# dual-led-wireless-dimmer-rev-c.net
KiCad netlist of a schematic drawn in EAGLE
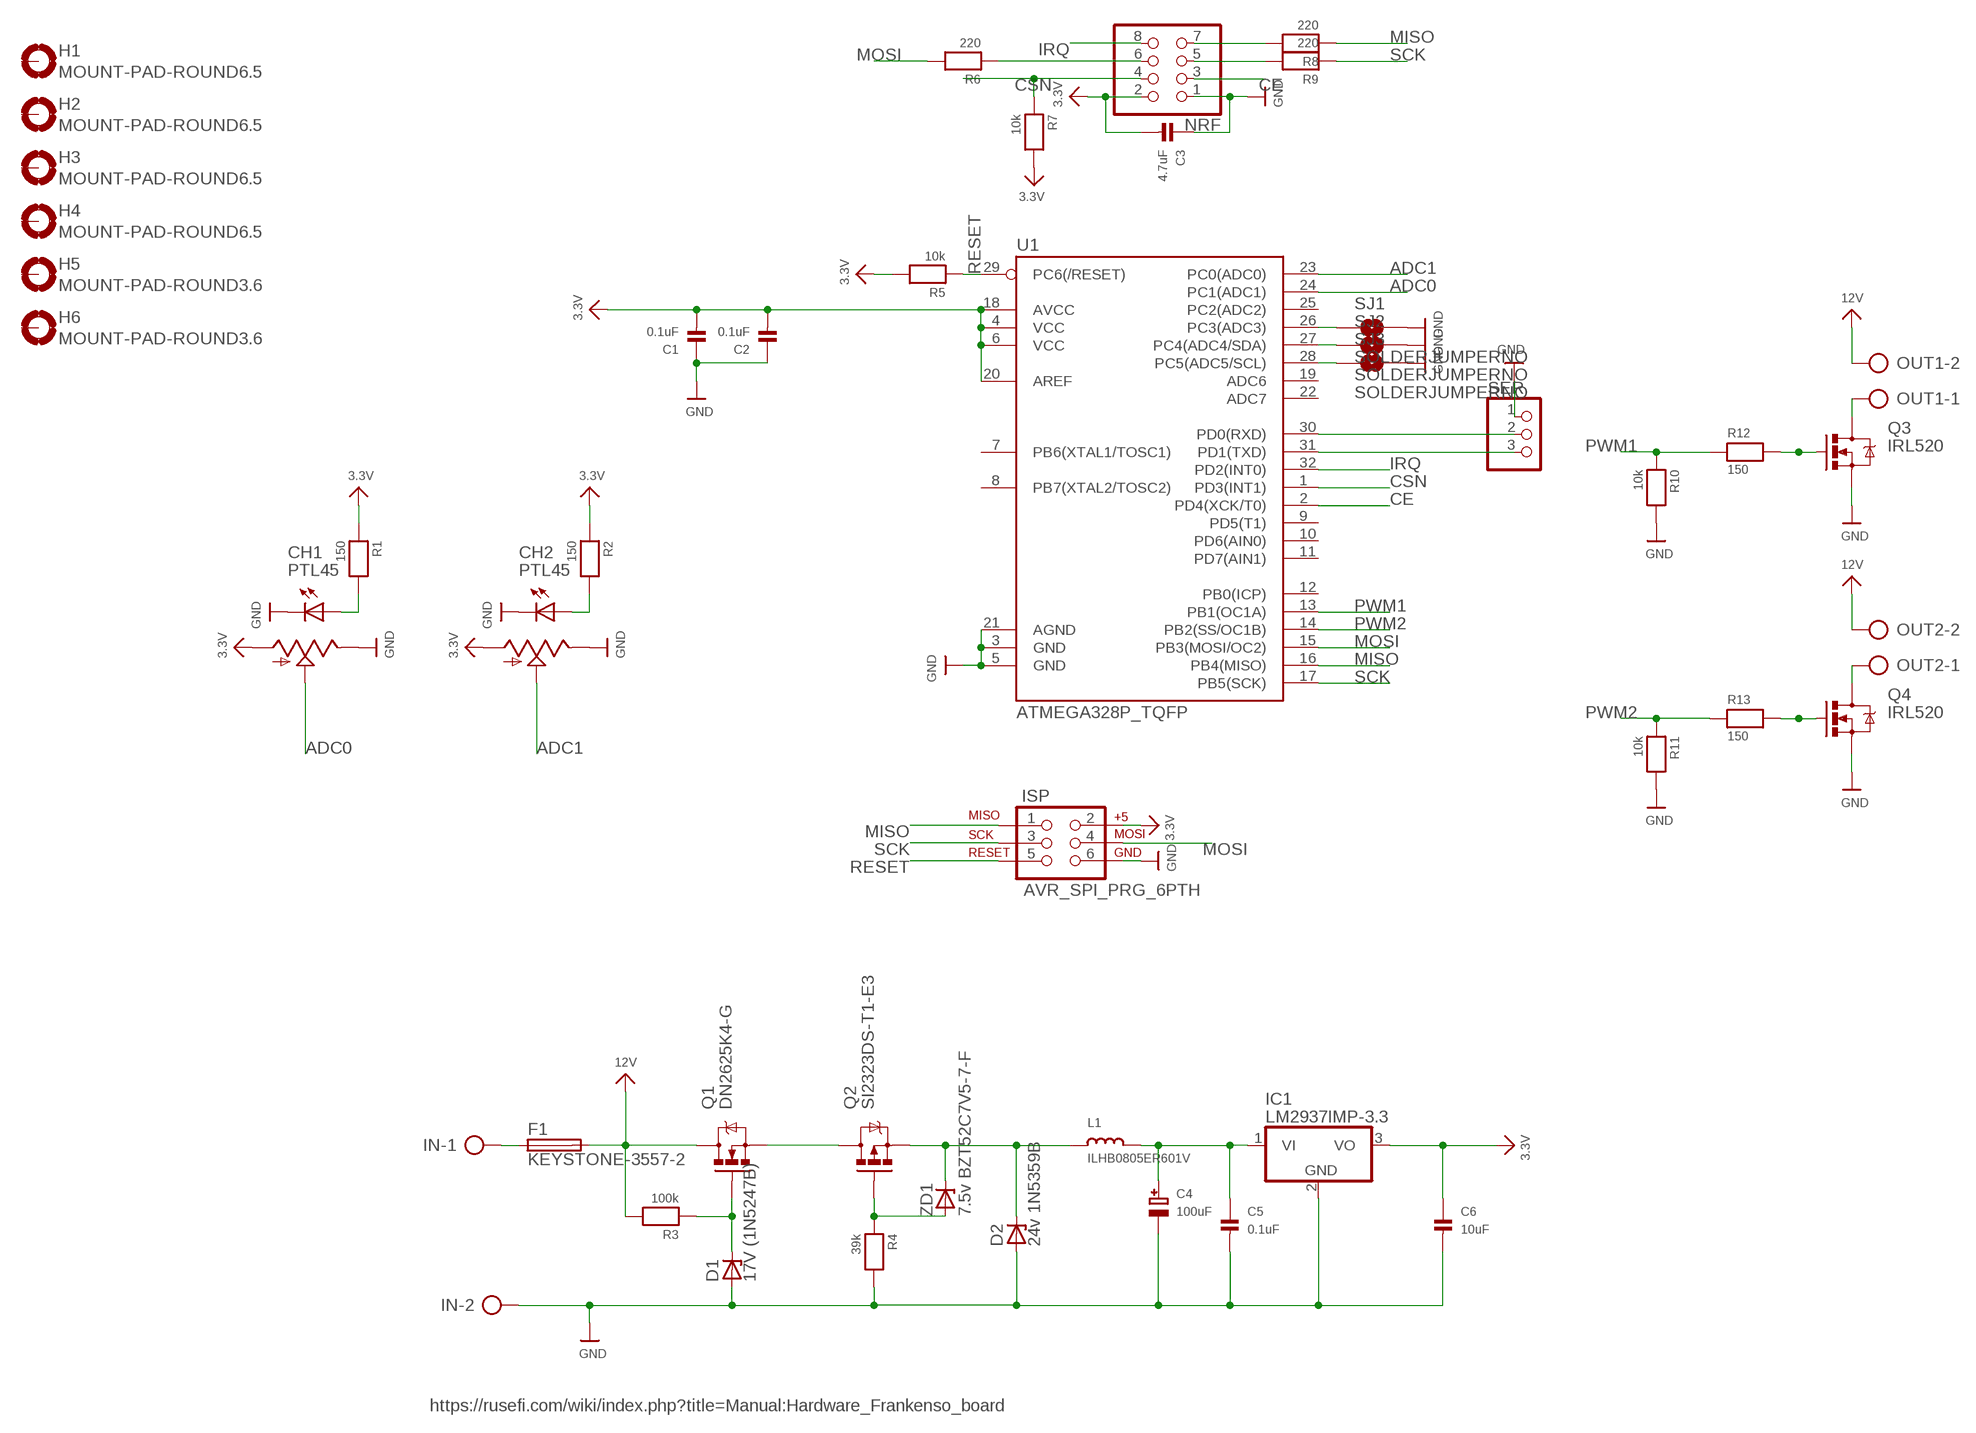
[diagram p0: schematic, sheet 1]

(export (version "E")
  (design (tool "Eeschema 10.0.6"))
  (components
    (comp (ref "C1")
      (value "0.1uF")
      (footprint "eagle-import:0805")
      (libsource (lib "eagle-import") (part "CAP_CERAMIC0805"))
    )
    (comp (ref "C2")
      (value "0.1uF")
      (footprint "eagle-import:0805")
      (libsource (lib "eagle-import") (part "CAP_CERAMIC0805"))
    )
    (comp (ref "C3")
      (value "4.7uF")
      (footprint "eagle-import:0805")
      (libsource (lib "eagle-import") (part "CAP_CERAMIC0805"))
    )
    (comp (ref "C4")
      (value "100uF")
      (footprint "eagle-import:PANASONIC_D")
      (libsource (lib "eagle-import") (part "CAP_ELECTROLYTICPANASONIC_D"))
    )
    (comp (ref "C5")
      (value "0.1uF")
      (footprint "eagle-import:0805")
      (libsource (lib "eagle-import") (part "CAP_CERAMIC0805"))
    )
    (comp (ref "C6")
      (value "10uF")
      (footprint "eagle-import:0805")
      (libsource (lib "eagle-import") (part "CAP_CERAMIC0805"))
    )
    (comp (ref "CH1")
      (value "PTL45")
      (footprint "eagle-import:BOURNS-PTL45")
      (fields (field (name "SPICEPREFIX") "C"))
      (libsource (lib "eagle-import") (part "PTL45"))
    )
    (comp (ref "CH2")
      (value "PTL45")
      (footprint "eagle-import:BOURNS-PTL45")
      (libsource (lib "eagle-import") (part "PTL45"))
    )
    (comp (ref "D1")
      (value "17V (1N5247B)")
      (footprint "eagle-import:ZDIO-5")
      (libsource (lib "eagle-import") (part "ZENER-DIODEZD-5"))
    )
    (comp (ref "D2")
      (value "24v 1N5359B")
      (footprint "eagle-import:DO41Z10")
      (libsource (lib "eagle-import") (part "ZPY"))
    )
    (comp (ref "F1")
      (value "KEYSTONE-3557-2")
      (footprint "eagle-import:KEYSTONE-3557-2")
      (libsource (lib "eagle-import") (part "KEYSTONE-3557-2"))
    )
    (comp (ref "H1")
      (value "MOUNT-PAD-ROUND6.5")
      (footprint "eagle-import:6,5-PAD")
      (libsource (lib "eagle-import") (part "MOUNT-PAD-ROUND6.5"))
    )
    (comp (ref "H2")
      (value "MOUNT-PAD-ROUND6.5")
      (footprint "eagle-import:6,5-PAD")
      (libsource (lib "eagle-import") (part "MOUNT-PAD-ROUND6.5"))
    )
    (comp (ref "H3")
      (value "MOUNT-PAD-ROUND6.5")
      (footprint "eagle-import:6,5-PAD")
      (libsource (lib "eagle-import") (part "MOUNT-PAD-ROUND6.5"))
    )
    (comp (ref "H4")
      (value "MOUNT-PAD-ROUND6.5")
      (footprint "eagle-import:6,5-PAD")
      (libsource (lib "eagle-import") (part "MOUNT-PAD-ROUND6.5"))
    )
    (comp (ref "H5")
      (value "MOUNT-PAD-ROUND3.6")
      (footprint "eagle-import:3,6-PAD")
      (libsource (lib "eagle-import") (part "MOUNT-PAD-ROUND3.6"))
    )
    (comp (ref "H6")
      (value "MOUNT-PAD-ROUND3.6")
      (footprint "eagle-import:3,6-PAD")
      (libsource (lib "eagle-import") (part "MOUNT-PAD-ROUND3.6"))
    )
    (comp (ref "IC1")
      (value "LM2937IMP-3.3")
      (footprint "eagle-import:TO263-3")
      (libsource (lib "eagle-import") (part "LM2937"))
    )
    (comp (ref "IN")
      (value "AK500/2-H")
      (footprint "eagle-import:AK500_2-H")
      (libsource (lib "eagle-import") (part "AK500/2-H"))
    )
    (comp (ref "ISP")
      (value "AVR_SPI_PRG_6PTH")
      (footprint "eagle-import:2X3")
      (libsource (lib "eagle-import") (part "AVR_SPI_PRG_6PTH"))
    )
    (comp (ref "L1")
      (value "ILHB0805ER601V")
      (footprint "eagle-import:0805")
      (libsource (lib "eagle-import") (part "INDUCTOR0805"))
    )
    (comp (ref "NRF")
      (value "PINHD-2X4")
      (footprint "eagle-import:2X04")
      (libsource (lib "eagle-import") (part "PINHD-2X4"))
    )
    (comp (ref "OUT1")
      (value "AK500/2-H")
      (footprint "eagle-import:AK500_2-H")
      (libsource (lib "eagle-import") (part "AK500/2-H"))
    )
    (comp (ref "OUT2")
      (value "AK500/2-H")
      (footprint "eagle-import:AK500_2-H")
      (libsource (lib "eagle-import") (part "AK500/2-H"))
    )
    (comp (ref "Q1")
      (value "DN2625K4-G")
      (footprint "eagle-import:DPAK")
      (libsource (lib "eagle-import") (part "MOSFET-NCHANNELFDD8780"))
    )
    (comp (ref "Q2")
      (value "SI2323DS-T1-E3")
      (footprint "eagle-import:SOT23-3")
      (libsource (lib "eagle-import") (part "MOSFET-PCHANNEL"))
    )
    (comp (ref "Q3")
      (value "IRL520")
      (footprint "eagle-import:TO220V")
      (libsource (lib "eagle-import") (part "keves-ng_1429743_MOSFET-NCHANNELFQP30N06L"))
    )
    (comp (ref "Q4")
      (value "IRL520")
      (footprint "eagle-import:TO220V")
      (libsource (lib "eagle-import") (part "keves-ng_1429743_MOSFET-NCHANNELFQP30N06L"))
    )
    (comp (ref "R1")
      (value "150")
      (footprint "eagle-import:0805")
      (libsource (lib "eagle-import") (part "RESISTOR0805"))
    )
    (comp (ref "R2")
      (value "150")
      (footprint "eagle-import:0805")
      (libsource (lib "eagle-import") (part "RESISTOR0805"))
    )
    (comp (ref "R3")
      (value "100k")
      (footprint "eagle-import:0805")
      (libsource (lib "eagle-import") (part "RESISTOR0805"))
    )
    (comp (ref "R4")
      (value "39k")
      (footprint "eagle-import:0805")
      (libsource (lib "eagle-import") (part "RESISTOR0805"))
    )
    (comp (ref "R5")
      (value "10k")
      (footprint "eagle-import:0805")
      (libsource (lib "eagle-import") (part "RESISTOR0805"))
    )
    (comp (ref "R6")
      (value "220")
      (footprint "eagle-import:0805")
      (libsource (lib "eagle-import") (part "RESISTOR0805"))
    )
    (comp (ref "R7")
      (value "10k")
      (footprint "eagle-import:0805")
      (libsource (lib "eagle-import") (part "RESISTOR0805"))
    )
    (comp (ref "R8")
      (value "220")
      (footprint "eagle-import:0805")
      (libsource (lib "eagle-import") (part "RESISTOR0805"))
    )
    (comp (ref "R9")
      (value "220")
      (footprint "eagle-import:0805")
      (libsource (lib "eagle-import") (part "RESISTOR0805"))
    )
    (comp (ref "R10")
      (value "10k")
      (footprint "eagle-import:0805")
      (libsource (lib "eagle-import") (part "RESISTOR0805"))
    )
    (comp (ref "R11")
      (value "10k")
      (footprint "eagle-import:0805")
      (libsource (lib "eagle-import") (part "RESISTOR0805"))
    )
    (comp (ref "R12")
      (value "150")
      (footprint "eagle-import:0805")
      (libsource (lib "eagle-import") (part "RESISTOR0805"))
    )
    (comp (ref "R13")
      (value "150")
      (footprint "eagle-import:0805")
      (libsource (lib "eagle-import") (part "RESISTOR0805"))
    )
    (comp (ref "SER")
      (value "PINHD-1X3")
      (footprint "eagle-import:1X03")
      (libsource (lib "eagle-import") (part "PINHD-1X3"))
    )
    (comp (ref "SJ1")
      (value "SOLDERJUMPERNO")
      (footprint "eagle-import:SJ_2S-NO")
      (libsource (lib "eagle-import") (part "SOLDERJUMPERNO"))
    )
    (comp (ref "SJ2")
      (value "SOLDERJUMPERNO")
      (footprint "eagle-import:SJ_2S-NO")
      (libsource (lib "eagle-import") (part "SOLDERJUMPERNO"))
    )
    (comp (ref "SJ3")
      (value "SOLDERJUMPERNO")
      (footprint "eagle-import:SJ_2S-NO")
      (libsource (lib "eagle-import") (part "SOLDERJUMPERNO"))
    )
    (comp (ref "U1")
      (value "ATMEGA328P_TQFP")
      (footprint "eagle-import:TQFP32-08")
      (libsource (lib "eagle-import") (part "ATMEGA328P_TQFP"))
    )
    (comp (ref "ZD1")
      (value "7.5v BZT52C7V5-7-F")
      (footprint "eagle-import:SOD123")
      (libsource (lib "eagle-import") (part "ZD-SOD123"))
    )
  )
  (nets
    (net (code "1") (name "/ADC0") (class "Default")
      (node (ref "CH1") (pin "2") (pinfunction "S_2") (pintype "passive"))
      (node (ref "U1") (pin "24") (pinfunction "PC1(ADC1)_24") (pintype "bidirectional"))
    )
    (net (code "2") (name "/ADC1") (class "Default")
      (node (ref "CH2") (pin "2") (pinfunction "S_2") (pintype "passive"))
      (node (ref "U1") (pin "23") (pinfunction "PC0(ADC0)_23") (pintype "bidirectional"))
    )
    (net (code "3") (name "/CE") (class "Default")
      (node (ref "NRF") (pin "3") (pinfunction "3_3") (pintype "passive"))
      (node (ref "U1") (pin "2") (pinfunction "PD4(XCK/T0)_2") (pintype "bidirectional"))
    )
    (net (code "4") (name "/CSN") (class "Default")
      (node (ref "NRF") (pin "4") (pinfunction "4_4") (pintype "passive"))
      (node (ref "R7") (pin "1") (pinfunction "1_1") (pintype "passive"))
      (node (ref "U1") (pin "1") (pinfunction "PD3(INT1)_1") (pintype "bidirectional"))
    )
    (net (code "5") (name "/IRQ") (class "Default")
      (node (ref "NRF") (pin "8") (pinfunction "8_8") (pintype "passive"))
      (node (ref "U1") (pin "32") (pinfunction "PD2(INT0)_32") (pintype "bidirectional"))
    )
    (net (code "6") (name "/MISO") (class "Default")
      (node (ref "ISP") (pin "1") (pinfunction "1_1") (pintype "passive"))
      (node (ref "R8") (pin "1") (pinfunction "1_1") (pintype "passive"))
      (node (ref "U1") (pin "16") (pinfunction "PB4(MISO)_16") (pintype "bidirectional"))
    )
    (net (code "7") (name "/MOSI") (class "Default")
      (node (ref "ISP") (pin "4") (pinfunction "4_4") (pintype "passive"))
      (node (ref "R6") (pin "2") (pinfunction "2_2") (pintype "passive"))
      (node (ref "U1") (pin "15") (pinfunction "PB3(MOSI/OC2)_15") (pintype "bidirectional"))
    )
    (net (code "8") (name "/PWM1") (class "Default")
      (node (ref "R10") (pin "1") (pinfunction "1_1") (pintype "passive"))
      (node (ref "R12") (pin "1") (pinfunction "1_1") (pintype "passive"))
      (node (ref "U1") (pin "13") (pinfunction "PB1(OC1A)_13") (pintype "bidirectional"))
    )
    (net (code "9") (name "/PWM2") (class "Default")
      (node (ref "R11") (pin "1") (pinfunction "1_1") (pintype "passive"))
      (node (ref "R13") (pin "1") (pinfunction "1_1") (pintype "passive"))
      (node (ref "U1") (pin "14") (pinfunction "PB2(SS/OC1B)_14") (pintype "bidirectional"))
    )
    (net (code "10") (name "/RESET") (class "Default")
      (node (ref "ISP") (pin "5") (pinfunction "5_5") (pintype "passive"))
      (node (ref "R5") (pin "1") (pinfunction "1_1") (pintype "passive"))
      (node (ref "U1") (pin "29") (pinfunction "PC6(/RESET)_29") (pintype "bidirectional"))
    )
    (net (code "11") (name "/SCK") (class "Default")
      (node (ref "ISP") (pin "3") (pinfunction "3_3") (pintype "passive"))
      (node (ref "R9") (pin "1") (pinfunction "1_1") (pintype "passive"))
      (node (ref "U1") (pin "17") (pinfunction "PB5(SCK)_17") (pintype "bidirectional"))
    )
    (net (code "12") (name "3.3V") (class "Default")
      (node (ref "C1") (pin "2") (pinfunction "P$2_2") (pintype "passive"))
      (node (ref "C2") (pin "2") (pinfunction "P$2_2") (pintype "passive"))
      (node (ref "C3") (pin "2") (pinfunction "P$2_2") (pintype "passive"))
      (node (ref "C6") (pin "1") (pinfunction "P$1_1") (pintype "passive"))
      (node (ref "CH1") (pin "1") (pinfunction "A_1") (pintype "passive"))
      (node (ref "CH2") (pin "1") (pinfunction "A_1") (pintype "passive"))
      (node (ref "IC1") (pin "3") (pinfunction "VO_3") (pintype "passive"))
      (node (ref "ISP") (pin "2") (pinfunction "2_2") (pintype "passive"))
      (node (ref "NRF") (pin "2") (pinfunction "2_2") (pintype "passive"))
      (node (ref "R1") (pin "1") (pinfunction "1_1") (pintype "passive"))
      (node (ref "R2") (pin "1") (pinfunction "1_1") (pintype "passive"))
      (node (ref "R5") (pin "2") (pinfunction "2_2") (pintype "passive"))
      (node (ref "R7") (pin "2") (pinfunction "2_2") (pintype "passive"))
      (node (ref "U1") (pin "18") (pinfunction "AVCC_18") (pintype "bidirectional"))
      (node (ref "U1") (pin "20") (pinfunction "AREF_20") (pintype "bidirectional"))
      (node (ref "U1") (pin "4") (pinfunction "VCC_4") (pintype "bidirectional"))
      (node (ref "U1") (pin "6") (pinfunction "VCC_6") (pintype "bidirectional"))
    )
    (net (code "13") (name "12V") (class "Default")
      (node (ref "F1") (pin "R1") (pinfunction "2_R1") (pintype "passive"))
      (node (ref "F1") (pin "R2") (pinfunction "2_R2") (pintype "passive"))
      (node (ref "OUT1") (pin "2") (pinfunction "KL_2") (pintype "passive"))
      (node (ref "OUT2") (pin "2") (pinfunction "KL_2") (pintype "passive"))
      (node (ref "Q1") (pin "4") (pinfunction "D_4") (pintype "passive"))
      (node (ref "R3") (pin "2") (pinfunction "2_2") (pintype "passive"))
    )
    (net (code "14") (name "GND") (class "Default")
      (node (ref "C1") (pin "1") (pinfunction "P$1_1") (pintype "passive"))
      (node (ref "C2") (pin "1") (pinfunction "P$1_1") (pintype "passive"))
      (node (ref "C3") (pin "1") (pinfunction "P$1_1") (pintype "passive"))
      (node (ref "C4") (pin "-") (pinfunction "-_-") (pintype "passive"))
      (node (ref "C5") (pin "2") (pinfunction "P$2_2") (pintype "passive"))
      (node (ref "C6") (pin "2") (pinfunction "P$2_2") (pintype "passive"))
      (node (ref "CH1") (pin "3") (pinfunction "E_3") (pintype "passive"))
      (node (ref "CH1") (pin "E") (pinfunction "LED-_E") (pintype "passive"))
      (node (ref "CH2") (pin "3") (pinfunction "E_3") (pintype "passive"))
      (node (ref "CH2") (pin "E") (pinfunction "LED-_E") (pintype "passive"))
      (node (ref "D1") (pin "A") (pinfunction "A_A") (pintype "passive"))
      (node (ref "D2") (pin "A") (pinfunction "A_A") (pintype "passive"))
      (node (ref "IC1") (pin "2") (pinfunction "GND_2") (pintype "passive"))
      (node (ref "IN") (pin "2") (pinfunction "KL_2") (pintype "passive"))
      (node (ref "ISP") (pin "6") (pinfunction "6_6") (pintype "passive"))
      (node (ref "NRF") (pin "1") (pinfunction "1_1") (pintype "passive"))
      (node (ref "Q3") (pin "3") (pinfunction "S_3") (pintype "passive"))
      (node (ref "Q4") (pin "3") (pinfunction "S_3") (pintype "passive"))
      (node (ref "R10") (pin "2") (pinfunction "2_2") (pintype "passive"))
      (node (ref "R11") (pin "2") (pinfunction "2_2") (pintype "passive"))
      (node (ref "R4") (pin "2") (pinfunction "2_2") (pintype "passive"))
      (node (ref "SER") (pin "1") (pinfunction "1_1") (pintype "passive"))
      (node (ref "SJ1") (pin "2") (pinfunction "2_2") (pintype "passive"))
      (node (ref "SJ2") (pin "2") (pinfunction "2_2") (pintype "passive"))
      (node (ref "SJ3") (pin "2") (pinfunction "2_2") (pintype "passive"))
      (node (ref "U1") (pin "21") (pinfunction "AGND_21") (pintype "bidirectional"))
      (node (ref "U1") (pin "3") (pinfunction "GND_3") (pintype "bidirectional"))
      (node (ref "U1") (pin "5") (pinfunction "GND_5") (pintype "bidirectional"))
    )
    (net (code "15") (name "Net-(C5-P$1)") (class "Default")
      (node (ref "C4") (pin "+") (pinfunction "+_+") (pintype "passive"))
      (node (ref "C5") (pin "1") (pinfunction "P$1_1") (pintype "passive"))
      (node (ref "IC1") (pin "1") (pinfunction "VI_1") (pintype "input"))
      (node (ref "L1") (pin "2") (pinfunction "2_2") (pintype "passive"))
    )
    (net (code "16") (name "Net-(CH1-LED+)") (class "Default")
      (node (ref "CH1") (pin "B") (pinfunction "LED+_B") (pintype "passive"))
      (node (ref "R1") (pin "2") (pinfunction "2_2") (pintype "passive"))
    )
    (net (code "17") (name "Net-(CH2-LED+)") (class "Default")
      (node (ref "CH2") (pin "B") (pinfunction "LED+_B") (pintype "passive"))
      (node (ref "R2") (pin "2") (pinfunction "2_2") (pintype "passive"))
    )
    (net (code "18") (name "Net-(INA-KL)") (class "Default")
      (node (ref "F1") (pin "L1") (pinfunction "1_L1") (pintype "passive"))
      (node (ref "F1") (pin "L2") (pinfunction "1_L2") (pintype "passive"))
      (node (ref "IN") (pin "1") (pinfunction "KL_1") (pintype "passive"))
    )
    (net (code "19") (name "Net-(NRF-Pad5)") (class "Default")
      (node (ref "NRF") (pin "5") (pinfunction "5_5") (pintype "passive"))
      (node (ref "R9") (pin "2") (pinfunction "2_2") (pintype "passive"))
    )
    (net (code "20") (name "Net-(NRF-Pad6)") (class "Default")
      (node (ref "NRF") (pin "6") (pinfunction "6_6") (pintype "passive"))
      (node (ref "R6") (pin "1") (pinfunction "1_1") (pintype "passive"))
    )
    (net (code "21") (name "Net-(NRF-Pad7)") (class "Default")
      (node (ref "NRF") (pin "7") (pinfunction "7_7") (pintype "passive"))
      (node (ref "R8") (pin "2") (pinfunction "2_2") (pintype "passive"))
    )
    (net (code "22") (name "Net-(OUT1A-KL)") (class "Default")
      (node (ref "OUT1") (pin "1") (pinfunction "KL_1") (pintype "passive"))
      (node (ref "Q3") (pin "2") (pinfunction "D_2") (pintype "passive"))
    )
    (net (code "23") (name "Net-(OUT2A-KL)") (class "Default")
      (node (ref "OUT2") (pin "1") (pinfunction "KL_1") (pintype "passive"))
      (node (ref "Q4") (pin "2") (pinfunction "D_2") (pintype "passive"))
    )
    (net (code "24") (name "Net-(Q1-G)") (class "Default")
      (node (ref "D1") (pin "C") (pinfunction "C_C") (pintype "passive"))
      (node (ref "Q1") (pin "1") (pinfunction "G_1") (pintype "passive"))
      (node (ref "R3") (pin "1") (pinfunction "1_1") (pintype "passive"))
    )
    (net (code "25") (name "Net-(Q1-S)") (class "Default")
      (node (ref "Q1") (pin "3") (pinfunction "S_3") (pintype "passive"))
      (node (ref "Q2") (pin "3") (pinfunction "D_3") (pintype "passive"))
    )
    (net (code "26") (name "Net-(Q2-G)") (class "Default")
      (node (ref "Q2") (pin "1") (pinfunction "G_1") (pintype "passive"))
      (node (ref "R4") (pin "1") (pinfunction "1_1") (pintype "passive"))
      (node (ref "ZD1") (pin "A") (pinfunction "A_A") (pintype "passive"))
    )
    (net (code "27") (name "Net-(Q2-S)") (class "Default")
      (node (ref "D2") (pin "C") (pinfunction "C_C") (pintype "passive"))
      (node (ref "L1") (pin "1") (pinfunction "1_1") (pintype "passive"))
      (node (ref "Q2") (pin "2") (pinfunction "S_2") (pintype "passive"))
      (node (ref "ZD1") (pin "C") (pinfunction "C_C") (pintype "passive"))
    )
    (net (code "28") (name "Net-(Q3-G)") (class "Default")
      (node (ref "Q3") (pin "1") (pinfunction "G_1") (pintype "passive"))
      (node (ref "R12") (pin "2") (pinfunction "2_2") (pintype "passive"))
    )
    (net (code "29") (name "Net-(Q4-G)") (class "Default")
      (node (ref "Q4") (pin "1") (pinfunction "G_1") (pintype "passive"))
      (node (ref "R13") (pin "2") (pinfunction "2_2") (pintype "passive"))
    )
    (net (code "30") (name "Net-(U1-PC3(ADC3))") (class "Default")
      (node (ref "SJ1") (pin "1") (pinfunction "1_1") (pintype "passive"))
      (node (ref "U1") (pin "26") (pinfunction "PC3(ADC3)_26") (pintype "bidirectional"))
    )
    (net (code "31") (name "Net-(U1-PC4(ADC4{slash}SDA))") (class "Default")
      (node (ref "SJ2") (pin "1") (pinfunction "1_1") (pintype "passive"))
      (node (ref "U1") (pin "27") (pinfunction "PC4(ADC4/SDA)_27") (pintype "bidirectional"))
    )
    (net (code "32") (name "Net-(U1-PC5(ADC5{slash}SCL))") (class "Default")
      (node (ref "SJ3") (pin "1") (pinfunction "1_1") (pintype "passive"))
      (node (ref "U1") (pin "28") (pinfunction "PC5(ADC5/SCL)_28") (pintype "bidirectional"))
    )
    (net (code "33") (name "Net-(U1-PD0(RXD))") (class "Default")
      (node (ref "SER") (pin "2") (pinfunction "2_2") (pintype "passive"))
      (node (ref "U1") (pin "30") (pinfunction "PD0(RXD)_30") (pintype "bidirectional"))
    )
    (net (code "34") (name "Net-(U1-PD1(TXD))") (class "Default")
      (node (ref "SER") (pin "3") (pinfunction "3_3") (pintype "passive"))
      (node (ref "U1") (pin "31") (pinfunction "PD1(TXD)_31") (pintype "bidirectional"))
    )
    (net (code "35") (name "unconnected-(H1-MOUNT-PadB6,5)") (class "Default")
      (node (ref "H1") (pin "B6,5") (pinfunction "MOUNT_B6,5") (pintype "passive"))
    )
    (net (code "36") (name "unconnected-(H2-MOUNT-PadB6,5)") (class "Default")
      (node (ref "H2") (pin "B6,5") (pinfunction "MOUNT_B6,5") (pintype "passive"))
    )
    (net (code "37") (name "unconnected-(H3-MOUNT-PadB6,5)") (class "Default")
      (node (ref "H3") (pin "B6,5") (pinfunction "MOUNT_B6,5") (pintype "passive"))
    )
    (net (code "38") (name "unconnected-(H4-MOUNT-PadB6,5)") (class "Default")
      (node (ref "H4") (pin "B6,5") (pinfunction "MOUNT_B6,5") (pintype "passive"))
    )
    (net (code "39") (name "unconnected-(H5-MOUNT-PadB3,6)") (class "Default")
      (node (ref "H5") (pin "B3,6") (pinfunction "MOUNT_B3,6") (pintype "passive"))
    )
    (net (code "40") (name "unconnected-(H6-MOUNT-PadB3,6)") (class "Default")
      (node (ref "H6") (pin "B3,6") (pinfunction "MOUNT_B3,6") (pintype "passive"))
    )
    (net (code "41") (name "unconnected-(U1-ADC6-Pad19)") (class "Default")
      (node (ref "U1") (pin "19") (pinfunction "ADC6_19") (pintype "bidirectional"))
    )
    (net (code "42") (name "unconnected-(U1-ADC7-Pad22)") (class "Default")
      (node (ref "U1") (pin "22") (pinfunction "ADC7_22") (pintype "bidirectional"))
    )
    (net (code "43") (name "unconnected-(U1-PB0(ICP)-Pad12)") (class "Default")
      (node (ref "U1") (pin "12") (pinfunction "PB0(ICP)_12") (pintype "bidirectional"))
    )
    (net (code "44") (name "unconnected-(U1-PB6(XTAL1{slash}TOSC1)-Pad7)") (class "Default")
      (node (ref "U1") (pin "7") (pinfunction "PB6(XTAL1/TOSC1)_7") (pintype "bidirectional"))
    )
    (net (code "45") (name "unconnected-(U1-PB7(XTAL2{slash}TOSC2)-Pad8)") (class "Default")
      (node (ref "U1") (pin "8") (pinfunction "PB7(XTAL2/TOSC2)_8") (pintype "bidirectional"))
    )
    (net (code "46") (name "unconnected-(U1-PC2(ADC2)-Pad25)") (class "Default")
      (node (ref "U1") (pin "25") (pinfunction "PC2(ADC2)_25") (pintype "bidirectional"))
    )
    (net (code "47") (name "unconnected-(U1-PD5(T1)-Pad9)") (class "Default")
      (node (ref "U1") (pin "9") (pinfunction "PD5(T1)_9") (pintype "bidirectional"))
    )
    (net (code "48") (name "unconnected-(U1-PD6(AIN0)-Pad10)") (class "Default")
      (node (ref "U1") (pin "10") (pinfunction "PD6(AIN0)_10") (pintype "bidirectional"))
    )
    (net (code "49") (name "unconnected-(U1-PD7(AIN1)-Pad11)") (class "Default")
      (node (ref "U1") (pin "11") (pinfunction "PD7(AIN1)_11") (pintype "bidirectional"))
    )
  )
)
